# POWER.net
KiCad netlist of a schematic drawn in Altium Designer
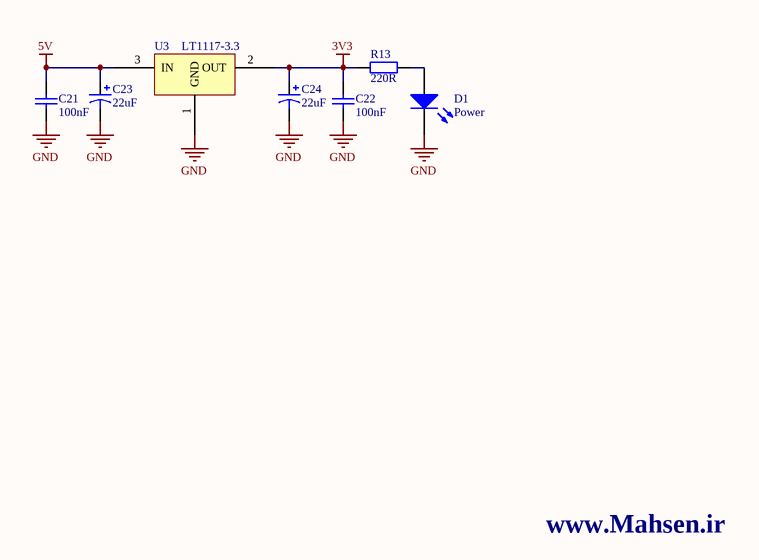
[diagram p0: POWER.SchDoc]

(export (version "E")
  (design (tool "Eeschema 10.0.6"))
  (components
    (comp (ref "C21")
      (value "100nF")
      (footprint "0805")
      (description "Capacitor")
      (fields (field (name "PUBLISHER") "Altium Limited"))
      (libsource (lib "Miscellaneous Devices") (part "Cap"))
    )
    (comp (ref "C22")
      (value "100nF")
      (footprint "0805")
      (description "Capacitor")
      (fields (field (name "PUBLISHER") "Altium Limited"))
      (libsource (lib "Miscellaneous Devices") (part "Cap"))
    )
    (comp (ref "C23")
      (value "22uF")
      (footprint "C0805")
      (description "Polarized Capacitor (Surface Mount)")
      (fields (field (name "PUBLISHER") "Altium Limited"))
      (libsource (lib "Miscellaneous Devices") (part "Cap Pol3"))
    )
    (comp (ref "C24")
      (value "22uF")
      (footprint "C0805")
      (description "Polarized Capacitor (Surface Mount)")
      (fields (field (name "PUBLISHER") "Altium Limited"))
      (libsource (lib "Miscellaneous Devices") (part "Cap Pol3"))
    )
    (comp (ref "D1")
      (value "Power")
      (footprint "3.5X2.8X1.9")
      (description "Typical BLUE SiC LED")
      (fields (field (name "PUBLISHER") "Altium Limited"))
      (libsource (lib "Miscellaneous Devices") (part "LED3"))
    )
    (comp (ref "R13")
      (value "220R")
      (footprint "0805")
      (description "Resistor")
      (fields (field (name "PUBLISHER") "Altium Limited"))
      (libsource (lib "Miscellaneous Devices") (part "Res2"))
    )
    (comp (ref "U3")
      (value "LT1117-3.3")
      (footprint "SOT223_4")
      (libsource (lib "Lotfi") (part "LT1117-3.3"))
    )
  )
  (nets
    (net (code "1") (name "3V3") (class "Default")
      (node (ref "C22") (pin "1") (pinfunction "1_1") (pintype "passive"))
      (node (ref "C24") (pin "1") (pinfunction "1_1") (pintype "passive"))
      (node (ref "R13") (pin "1") (pinfunction "1_1") (pintype "passive"))
      (node (ref "U3") (pin "2") (pinfunction "OUT_2") (pintype "passive"))
    )
    (net (code "2") (name "5V") (class "Default")
      (node (ref "C21") (pin "1") (pinfunction "1_1") (pintype "passive"))
      (node (ref "C23") (pin "1") (pinfunction "1_1") (pintype "passive"))
      (node (ref "U3") (pin "3") (pinfunction "IN_3") (pintype "passive"))
    )
    (net (code "3") (name "GND") (class "Default")
      (node (ref "C21") (pin "2") (pinfunction "2_2") (pintype "passive"))
      (node (ref "C22") (pin "2") (pinfunction "2_2") (pintype "passive"))
      (node (ref "C23") (pin "2") (pinfunction "2_2") (pintype "passive"))
      (node (ref "C24") (pin "2") (pinfunction "2_2") (pintype "passive"))
      (node (ref "D1") (pin "2") (pinfunction "K_2") (pintype "passive"))
      (node (ref "U3") (pin "1") (pinfunction "GND_1") (pintype "passive"))
    )
    (net (code "4") (name "Net-(D1-A)") (class "Default")
      (node (ref "D1") (pin "1") (pinfunction "A_1") (pintype "passive"))
      (node (ref "R13") (pin "2") (pinfunction "2_2") (pintype "passive"))
    )
  )
)
